# FLC-148_ptt_panel.net
KiCad netlist of a schematic drawn in EAGLE
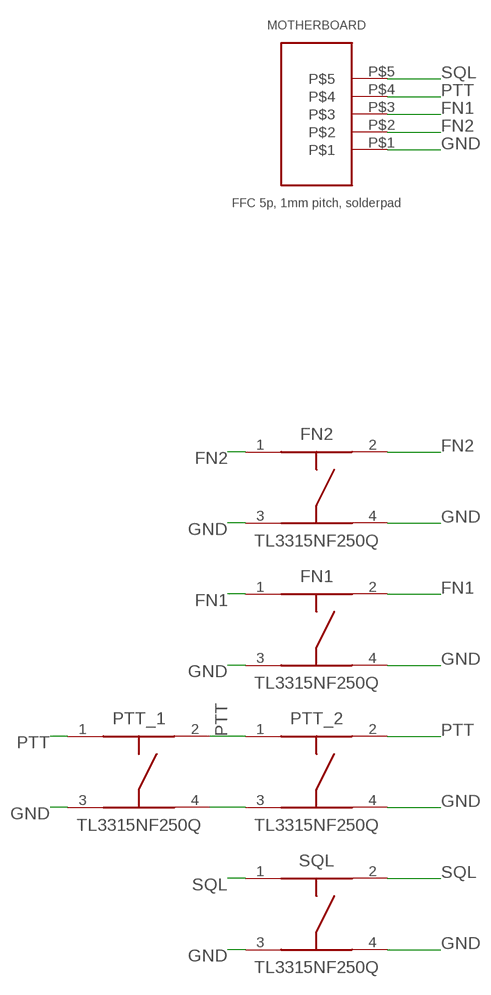
[diagram p0: schematic, sheet 1]

(export (version "E")
  (design (tool "Eeschema 10.0.6"))
  (components
    (comp (ref "FN1")
      (value "TL3315NF250Q")
      (footprint "eagle-import:SMT")
      (libsource (lib "eagle-import") (part "TL3315NF250Q"))
    )
    (comp (ref "FN2")
      (value "TL3315NF250Q")
      (footprint "eagle-import:SMT")
      (libsource (lib "eagle-import") (part "TL3315NF250Q"))
    )
    (comp (ref "MOTHERBOARD")
      (value "FFC 5p, 1mm pitch, solderpad")
      (footprint "eagle-import:FFC_1MM_5P")
      (libsource (lib "eagle-import") (part "FFC_1MM_5P"))
    )
    (comp (ref "PTT_1")
      (value "TL3315NF250Q")
      (footprint "eagle-import:SMT")
      (libsource (lib "eagle-import") (part "TL3315NF250Q"))
    )
    (comp (ref "PTT_2")
      (value "TL3315NF250Q")
      (footprint "eagle-import:SMT")
      (libsource (lib "eagle-import") (part "TL3315NF250Q"))
    )
    (comp (ref "SQL")
      (value "TL3315NF250Q")
      (footprint "eagle-import:SMT")
      (libsource (lib "eagle-import") (part "TL3315NF250Q"))
    )
  )
  (nets
    (net (code "1") (name "/FN1") (class "Default")
      (node (ref "FN1") (pin "1") (pinfunction "1_1") (pintype "bidirectional"))
      (node (ref "FN1") (pin "2") (pinfunction "2_2") (pintype "bidirectional"))
      (node (ref "MOTHERBOARD") (pin "P$3") (pinfunction "P$3_P$3") (pintype "bidirectional"))
    )
    (net (code "2") (name "/FN2") (class "Default")
      (node (ref "FN2") (pin "1") (pinfunction "1_1") (pintype "bidirectional"))
      (node (ref "FN2") (pin "2") (pinfunction "2_2") (pintype "bidirectional"))
      (node (ref "MOTHERBOARD") (pin "P$2") (pinfunction "P$2_P$2") (pintype "bidirectional"))
    )
    (net (code "3") (name "/GND") (class "Default")
      (node (ref "FN1") (pin "3") (pinfunction "3_3") (pintype "bidirectional"))
      (node (ref "FN1") (pin "4") (pinfunction "4_4") (pintype "bidirectional"))
      (node (ref "FN2") (pin "3") (pinfunction "3_3") (pintype "bidirectional"))
      (node (ref "FN2") (pin "4") (pinfunction "4_4") (pintype "bidirectional"))
      (node (ref "MOTHERBOARD") (pin "P$1") (pinfunction "P$1_P$1") (pintype "bidirectional"))
      (node (ref "PTT_1") (pin "3") (pinfunction "3_3") (pintype "bidirectional"))
      (node (ref "PTT_1") (pin "4") (pinfunction "4_4") (pintype "bidirectional"))
      (node (ref "PTT_2") (pin "3") (pinfunction "3_3") (pintype "bidirectional"))
      (node (ref "PTT_2") (pin "4") (pinfunction "4_4") (pintype "bidirectional"))
      (node (ref "SQL") (pin "3") (pinfunction "3_3") (pintype "bidirectional"))
      (node (ref "SQL") (pin "4") (pinfunction "4_4") (pintype "bidirectional"))
    )
    (net (code "4") (name "/PTT") (class "Default")
      (node (ref "MOTHERBOARD") (pin "P$4") (pinfunction "P$4_P$4") (pintype "bidirectional"))
      (node (ref "PTT_1") (pin "1") (pinfunction "1_1") (pintype "bidirectional"))
      (node (ref "PTT_1") (pin "2") (pinfunction "2_2") (pintype "bidirectional"))
      (node (ref "PTT_2") (pin "1") (pinfunction "1_1") (pintype "bidirectional"))
      (node (ref "PTT_2") (pin "2") (pinfunction "2_2") (pintype "bidirectional"))
    )
    (net (code "5") (name "/SQL") (class "Default")
      (node (ref "MOTHERBOARD") (pin "P$5") (pinfunction "P$5_P$5") (pintype "bidirectional"))
      (node (ref "SQL") (pin "1") (pinfunction "1_1") (pintype "bidirectional"))
      (node (ref "SQL") (pin "2") (pinfunction "2_2") (pintype "bidirectional"))
    )
  )
)
